# I2CBB-R2.net
KiCad netlist of a schematic drawn in EAGLE
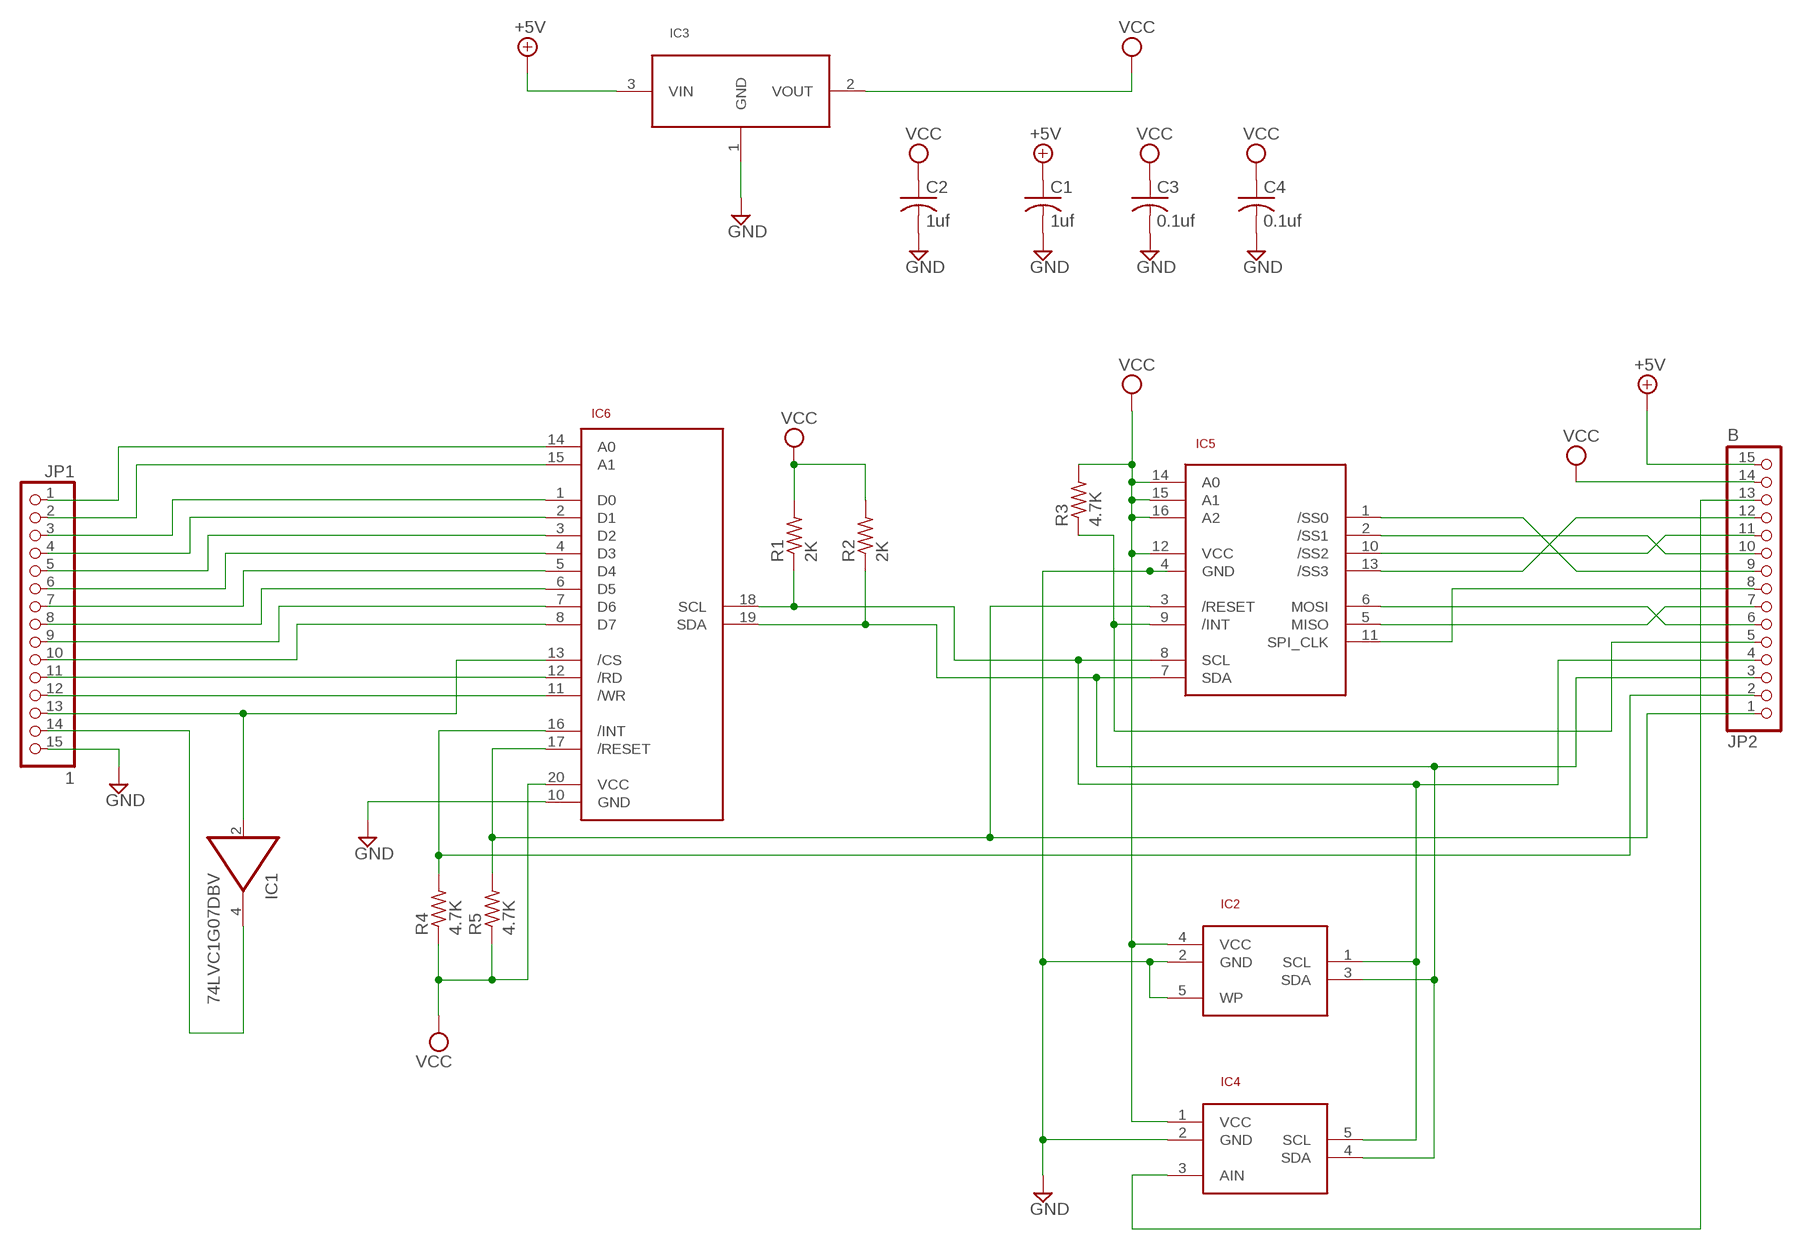
[diagram p0: schematic, sheet 1]

(export (version "E")
  (design (tool "Eeschema 10.0.6"))
  (components
    (comp (ref "C1")
      (value "1uf")
      (footprint "eagle-import:C0603")
      (libsource (lib "eagle-import") (part "C-USC0603"))
    )
    (comp (ref "C2")
      (value "1uf")
      (footprint "eagle-import:C0603")
      (libsource (lib "eagle-import") (part "C-USC0603"))
    )
    (comp (ref "C3")
      (value "0.1uf")
      (footprint "eagle-import:C0603")
      (libsource (lib "eagle-import") (part "C-USC0603"))
    )
    (comp (ref "C4")
      (value "0.1uf")
      (footprint "eagle-import:C0603")
      (libsource (lib "eagle-import") (part "C-USC0603"))
    )
    (comp (ref "IC1")
      (value "74LVC1G07DBV")
      (footprint "eagle-import:SOT23-5")
      (libsource (lib "eagle-import") (part "741G07DBVLVC"))
    )
    (comp (ref "IC2")
      (value "24AA64T")
      (footprint "eagle-import:SOT23-5")
      (libsource (lib "eagle-import") (part "24AA64T"))
    )
    (comp (ref "IC3")
      (value "MCP1700T")
      (footprint "eagle-import:SOT23")
      (libsource (lib "eagle-import") (part "MCP1700T"))
    )
    (comp (ref "IC4")
      (value "MCP3221")
      (footprint "eagle-import:SOT23-5")
      (libsource (lib "eagle-import") (part "MCP3221"))
    )
    (comp (ref "IC5")
      (value "SC18IS602")
      (footprint "eagle-import:TSSOP16")
      (libsource (lib "eagle-import") (part "SC18IS602"))
    )
    (comp (ref "IC6")
      (value "PCA9665")
      (footprint "eagle-import:TSSOP20")
      (libsource (lib "eagle-import") (part "PCA9665"))
    )
    (comp (ref "JP1")
      (value "1")
      (footprint "eagle-import:1X15")
      (libsource (lib "eagle-import") (part "PINHD-1X15"))
    )
    (comp (ref "JP2")
      (value "B")
      (footprint "eagle-import:1X15")
      (libsource (lib "eagle-import") (part "PINHD-1X15"))
    )
    (comp (ref "R1")
      (value "2K")
      (footprint "eagle-import:R0603")
      (libsource (lib "eagle-import") (part "R-US_R0603"))
    )
    (comp (ref "R2")
      (value "2K")
      (footprint "eagle-import:R0603")
      (libsource (lib "eagle-import") (part "R-US_R0603"))
    )
    (comp (ref "R3")
      (value "4.7K")
      (footprint "eagle-import:R0603")
      (libsource (lib "eagle-import") (part "R-US_R0603"))
    )
    (comp (ref "R4")
      (value "4.7K")
      (footprint "eagle-import:R0603")
      (libsource (lib "eagle-import") (part "R-US_R0603"))
    )
    (comp (ref "R5")
      (value "4.7K")
      (footprint "eagle-import:R0603")
      (libsource (lib "eagle-import") (part "R-US_R0603"))
    )
  )
  (nets
    (net (code "1") (name "+5V") (class "Default")
      (node (ref "C1") (pin "1") (pinfunction "1_1") (pintype "passive"))
      (node (ref "IC3") (pin "3") (pinfunction "VIN_3") (pintype "power_in"))
      (node (ref "JP2") (pin "15") (pinfunction "15_15") (pintype "passive"))
    )
    (net (code "2") (name "GND") (class "Default")
      (node (ref "C1") (pin "2") (pinfunction "2_2") (pintype "passive"))
      (node (ref "C2") (pin "2") (pinfunction "2_2") (pintype "passive"))
      (node (ref "C3") (pin "2") (pinfunction "2_2") (pintype "passive"))
      (node (ref "C4") (pin "2") (pinfunction "2_2") (pintype "passive"))
      (node (ref "IC2") (pin "2") (pinfunction "GND_2") (pintype "bidirectional"))
      (node (ref "IC2") (pin "5") (pinfunction "WP_5") (pintype "bidirectional"))
      (node (ref "IC3") (pin "1") (pinfunction "GND_1") (pintype "power_in"))
      (node (ref "IC4") (pin "2") (pinfunction "GND_2") (pintype "power_in"))
      (node (ref "IC5") (pin "4") (pinfunction "GND_4") (pintype "power_in"))
      (node (ref "IC6") (pin "10") (pinfunction "GND_10") (pintype "power_in"))
      (node (ref "JP1") (pin "15") (pinfunction "15_15") (pintype "passive"))
    )
    (net (code "3") (name "Net-(IC1A-I)") (class "Default")
      (node (ref "IC1") (pin "2") (pinfunction "I_2") (pintype "input"))
      (node (ref "IC6") (pin "13") (pinfunction "/CS_13") (pintype "input"))
      (node (ref "JP1") (pin "13") (pinfunction "13_13") (pintype "passive"))
    )
    (net (code "4") (name "Net-(IC1A-O)") (class "Default")
      (node (ref "IC1") (pin "4") (pinfunction "O_4") (pintype "open_collector"))
      (node (ref "JP1") (pin "14") (pinfunction "14_14") (pintype "passive"))
    )
    (net (code "5") (name "Net-(IC2-SCL)") (class "Default")
      (node (ref "IC2") (pin "1") (pinfunction "SCL_1") (pintype "bidirectional"))
      (node (ref "IC4") (pin "5") (pinfunction "SCL_5") (pintype "bidirectional"))
      (node (ref "IC5") (pin "8") (pinfunction "SCL_8") (pintype "bidirectional"))
      (node (ref "IC6") (pin "18") (pinfunction "SCL_18") (pintype "bidirectional"))
      (node (ref "JP2") (pin "4") (pinfunction "4_4") (pintype "passive"))
      (node (ref "R1") (pin "1") (pinfunction "1_1") (pintype "passive"))
    )
    (net (code "6") (name "Net-(IC2-SDA)") (class "Default")
      (node (ref "IC2") (pin "3") (pinfunction "SDA_3") (pintype "bidirectional"))
      (node (ref "IC4") (pin "4") (pinfunction "SDA_4") (pintype "bidirectional"))
      (node (ref "IC5") (pin "7") (pinfunction "SDA_7") (pintype "bidirectional"))
      (node (ref "IC6") (pin "19") (pinfunction "SDA_19") (pintype "bidirectional"))
      (node (ref "JP2") (pin "3") (pinfunction "3_3") (pintype "passive"))
      (node (ref "R2") (pin "1") (pinfunction "1_1") (pintype "passive"))
    )
    (net (code "7") (name "Net-(IC4-AIN)") (class "Default")
      (node (ref "IC4") (pin "3") (pinfunction "AIN_3") (pintype "input"))
      (node (ref "JP2") (pin "13") (pinfunction "13_13") (pintype "passive"))
    )
    (net (code "8") (name "Net-(IC5-MISO)") (class "Default")
      (node (ref "IC5") (pin "5") (pinfunction "MISO_5") (pintype "bidirectional"))
      (node (ref "JP2") (pin "7") (pinfunction "7_7") (pintype "passive"))
    )
    (net (code "9") (name "Net-(IC5-MOSI)") (class "Default")
      (node (ref "IC5") (pin "6") (pinfunction "MOSI_6") (pintype "bidirectional"))
      (node (ref "JP2") (pin "6") (pinfunction "6_6") (pintype "passive"))
    )
    (net (code "10") (name "Net-(IC5-SPI_CLK)") (class "Default")
      (node (ref "IC5") (pin "11") (pinfunction "SPI_CLK_11") (pintype "bidirectional"))
      (node (ref "JP2") (pin "8") (pinfunction "8_8") (pintype "passive"))
    )
    (net (code "11") (name "Net-(IC5-{slash}INT)") (class "Default")
      (node (ref "IC5") (pin "9") (pinfunction "/INT_9") (pintype "output"))
      (node (ref "JP2") (pin "5") (pinfunction "5_5") (pintype "passive"))
      (node (ref "R3") (pin "1") (pinfunction "1_1") (pintype "passive"))
    )
    (net (code "12") (name "Net-(IC5-{slash}RESET)") (class "Default")
      (node (ref "IC5") (pin "3") (pinfunction "/RESET_3") (pintype "input"))
      (node (ref "IC6") (pin "17") (pinfunction "/RESET_17") (pintype "input"))
      (node (ref "JP2") (pin "1") (pinfunction "1_1") (pintype "passive"))
      (node (ref "R5") (pin "2") (pinfunction "2_2") (pintype "passive"))
    )
    (net (code "13") (name "Net-(IC5-{slash}SS0)") (class "Default")
      (node (ref "IC5") (pin "1") (pinfunction "/SS0_1") (pintype "bidirectional"))
      (node (ref "JP2") (pin "9") (pinfunction "9_9") (pintype "passive"))
    )
    (net (code "14") (name "Net-(IC5-{slash}SS1)") (class "Default")
      (node (ref "IC5") (pin "2") (pinfunction "/SS1_2") (pintype "bidirectional"))
      (node (ref "JP2") (pin "10") (pinfunction "10_10") (pintype "passive"))
    )
    (net (code "15") (name "Net-(IC5-{slash}SS2)") (class "Default")
      (node (ref "IC5") (pin "10") (pinfunction "/SS2_10") (pintype "bidirectional"))
      (node (ref "JP2") (pin "11") (pinfunction "11_11") (pintype "passive"))
    )
    (net (code "16") (name "Net-(IC5-{slash}SS3)") (class "Default")
      (node (ref "IC5") (pin "13") (pinfunction "/SS3_13") (pintype "bidirectional"))
      (node (ref "JP2") (pin "12") (pinfunction "12_12") (pintype "passive"))
    )
    (net (code "17") (name "Net-(IC6-A0)") (class "Default")
      (node (ref "IC6") (pin "14") (pinfunction "A0_14") (pintype "input"))
      (node (ref "JP1") (pin "1") (pinfunction "1_1") (pintype "passive"))
    )
    (net (code "18") (name "Net-(IC6-A1)") (class "Default")
      (node (ref "IC6") (pin "15") (pinfunction "A1_15") (pintype "input"))
      (node (ref "JP1") (pin "2") (pinfunction "2_2") (pintype "passive"))
    )
    (net (code "19") (name "Net-(IC6-D0)") (class "Default")
      (node (ref "IC6") (pin "1") (pinfunction "D0_1") (pintype "bidirectional"))
      (node (ref "JP1") (pin "3") (pinfunction "3_3") (pintype "passive"))
    )
    (net (code "20") (name "Net-(IC6-D1)") (class "Default")
      (node (ref "IC6") (pin "2") (pinfunction "D1_2") (pintype "bidirectional"))
      (node (ref "JP1") (pin "4") (pinfunction "4_4") (pintype "passive"))
    )
    (net (code "21") (name "Net-(IC6-D2)") (class "Default")
      (node (ref "IC6") (pin "3") (pinfunction "D2_3") (pintype "bidirectional"))
      (node (ref "JP1") (pin "5") (pinfunction "5_5") (pintype "passive"))
    )
    (net (code "22") (name "Net-(IC6-D3)") (class "Default")
      (node (ref "IC6") (pin "4") (pinfunction "D3_4") (pintype "bidirectional"))
      (node (ref "JP1") (pin "6") (pinfunction "6_6") (pintype "passive"))
    )
    (net (code "23") (name "Net-(IC6-D4)") (class "Default")
      (node (ref "IC6") (pin "5") (pinfunction "D4_5") (pintype "bidirectional"))
      (node (ref "JP1") (pin "7") (pinfunction "7_7") (pintype "passive"))
    )
    (net (code "24") (name "Net-(IC6-D5)") (class "Default")
      (node (ref "IC6") (pin "6") (pinfunction "D5_6") (pintype "bidirectional"))
      (node (ref "JP1") (pin "8") (pinfunction "8_8") (pintype "passive"))
    )
    (net (code "25") (name "Net-(IC6-D6)") (class "Default")
      (node (ref "IC6") (pin "7") (pinfunction "D6_7") (pintype "bidirectional"))
      (node (ref "JP1") (pin "9") (pinfunction "9_9") (pintype "passive"))
    )
    (net (code "26") (name "Net-(IC6-D7)") (class "Default")
      (node (ref "IC6") (pin "8") (pinfunction "D7_8") (pintype "bidirectional"))
      (node (ref "JP1") (pin "10") (pinfunction "10_10") (pintype "passive"))
    )
    (net (code "27") (name "Net-(IC6-{slash}INT)") (class "Default")
      (node (ref "IC6") (pin "16") (pinfunction "/INT_16") (pintype "input"))
      (node (ref "JP2") (pin "2") (pinfunction "2_2") (pintype "passive"))
      (node (ref "R4") (pin "2") (pinfunction "2_2") (pintype "passive"))
    )
    (net (code "28") (name "Net-(IC6-{slash}RD)") (class "Default")
      (node (ref "IC6") (pin "12") (pinfunction "/RD_12") (pintype "input"))
      (node (ref "JP1") (pin "11") (pinfunction "11_11") (pintype "passive"))
    )
    (net (code "29") (name "Net-(IC6-{slash}WR)") (class "Default")
      (node (ref "IC6") (pin "11") (pinfunction "/WR_11") (pintype "input"))
      (node (ref "JP1") (pin "12") (pinfunction "12_12") (pintype "passive"))
    )
    (net (code "30") (name "VCC") (class "Default")
      (node (ref "C2") (pin "1") (pinfunction "1_1") (pintype "passive"))
      (node (ref "C3") (pin "1") (pinfunction "1_1") (pintype "passive"))
      (node (ref "C4") (pin "1") (pinfunction "1_1") (pintype "passive"))
      (node (ref "IC2") (pin "4") (pinfunction "VCC_4") (pintype "bidirectional"))
      (node (ref "IC3") (pin "2") (pinfunction "VOUT_2") (pintype "power_in"))
      (node (ref "IC4") (pin "1") (pinfunction "VCC_1") (pintype "power_in"))
      (node (ref "IC5") (pin "12") (pinfunction "VCC_12") (pintype "power_in"))
      (node (ref "IC5") (pin "14") (pinfunction "A0_14") (pintype "bidirectional"))
      (node (ref "IC5") (pin "15") (pinfunction "A1_15") (pintype "bidirectional"))
      (node (ref "IC5") (pin "16") (pinfunction "A2_16") (pintype "bidirectional"))
      (node (ref "IC6") (pin "20") (pinfunction "VCC_20") (pintype "power_in"))
      (node (ref "JP2") (pin "14") (pinfunction "14_14") (pintype "passive"))
      (node (ref "R1") (pin "2") (pinfunction "2_2") (pintype "passive"))
      (node (ref "R2") (pin "2") (pinfunction "2_2") (pintype "passive"))
      (node (ref "R3") (pin "2") (pinfunction "2_2") (pintype "passive"))
      (node (ref "R4") (pin "1") (pinfunction "1_1") (pintype "passive"))
      (node (ref "R5") (pin "1") (pinfunction "1_1") (pintype "passive"))
    )
  )
)
